# stm32f103_ethernet_shield.net
KiCad netlist of a schematic drawn in EAGLE
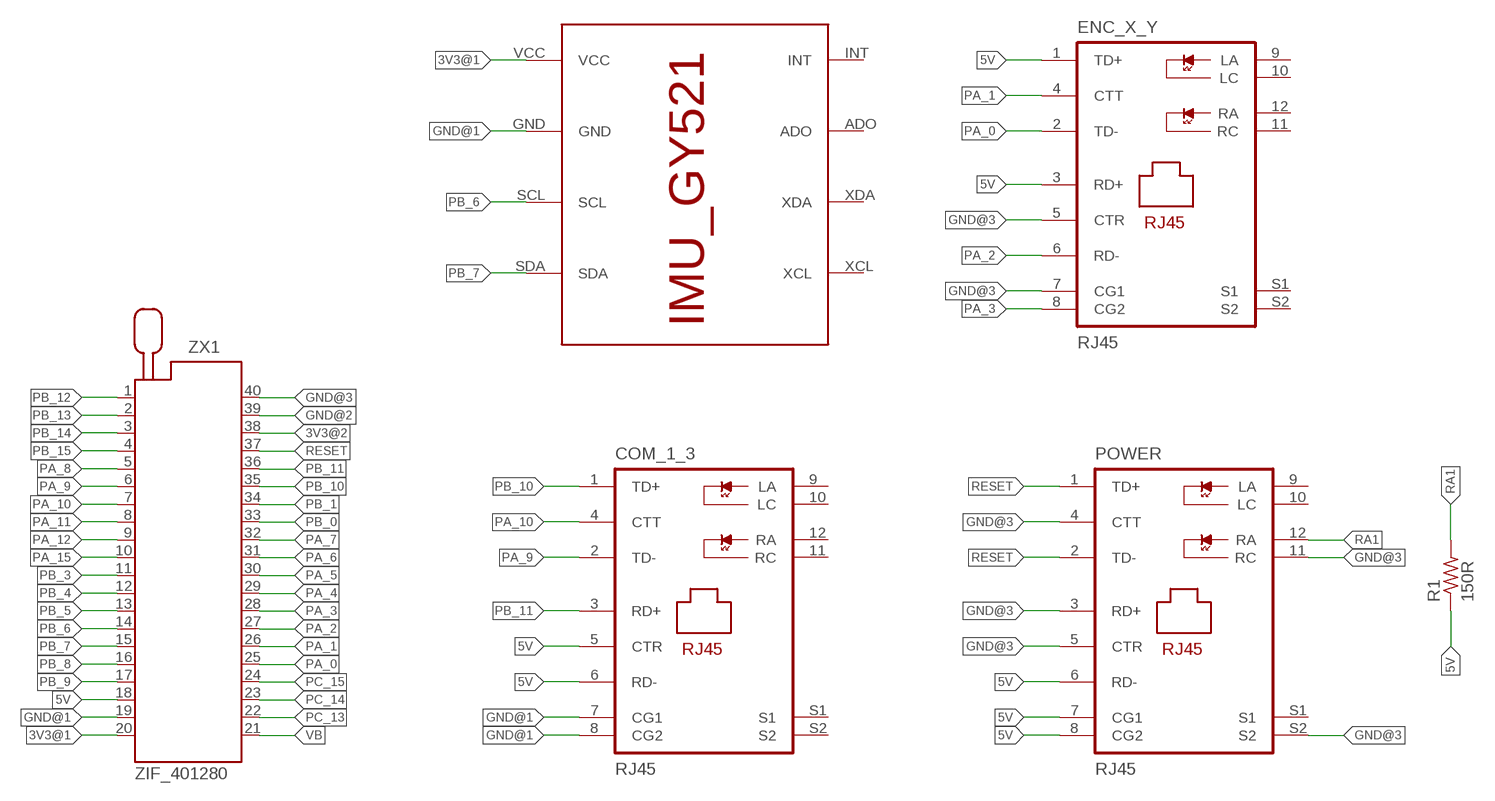
[diagram p0: schematic, sheet 1]

(export (version "E")
  (design (tool "Eeschema 10.0.6"))
  (components
    (comp (ref "COM_1_3")
      (value "RJ45")
      (footprint "eagle-import:J0-A_B_F")
      (libsource (lib "eagle-import") (part "RJ45_METAL_LEDS"))
    )
    (comp (ref "ENC_X_Y")
      (value "RJ45")
      (footprint "eagle-import:J0-A_B_F")
      (fields (field (name "SPICEPREFIX") "X"))
      (libsource (lib "eagle-import") (part "RJ45_METAL_LEDS"))
    )
    (comp (ref "MPU6050")
      (value "IMU_ROBOCON_GY521")
      (footprint "eagle-import:IMU_GY521")
      (libsource (lib "eagle-import") (part "IMU_ROBOCON_GY521"))
    )
    (comp (ref "POWER")
      (value "RJ45")
      (footprint "eagle-import:J0-A_B_F")
      (libsource (lib "eagle-import") (part "RJ45_METAL_LEDS"))
    )
    (comp (ref "R1")
      (value "150R")
      (footprint "eagle-import:0204_7")
      (libsource (lib "eagle-import") (part "RES-7"))
    )
    (comp (ref "ZX1")
      (value "ZIF_401280")
      (footprint "eagle-import:240-1280-00-0602J")
      (libsource (lib "eagle-import") (part "ZIF_401280"))
    )
  )
  (nets
    (net (code "1") (name "3V3@1") (class "Default")
      (node (ref "MPU6050") (pin "VCC") (pinfunction "VCC_VCC") (pintype "bidirectional"))
      (node (ref "ZX1") (pin "20") (pinfunction "20_20") (pintype "passive"))
    )
    (net (code "2") (name "3V3@2") (class "Default")
      (node (ref "ZX1") (pin "38") (pinfunction "38_38") (pintype "passive"))
    )
    (net (code "3") (name "5V") (class "Default")
      (node (ref "COM_1_3") (pin "5") (pinfunction "CTR_5") (pintype "passive"))
      (node (ref "COM_1_3") (pin "6") (pinfunction "RD-_6") (pintype "passive"))
      (node (ref "ENC_X_Y") (pin "1") (pinfunction "TD+_1") (pintype "passive"))
      (node (ref "ENC_X_Y") (pin "3") (pinfunction "RD+_3") (pintype "passive"))
      (node (ref "POWER") (pin "6") (pinfunction "RD-_6") (pintype "passive"))
      (node (ref "POWER") (pin "7") (pinfunction "CG1_7") (pintype "passive"))
      (node (ref "POWER") (pin "8") (pinfunction "CG2_8") (pintype "passive"))
      (node (ref "R1") (pin "1") (pinfunction "1_1") (pintype "passive"))
      (node (ref "ZX1") (pin "18") (pinfunction "18_18") (pintype "passive"))
    )
    (net (code "4") (name "GND@1") (class "Default")
      (node (ref "COM_1_3") (pin "7") (pinfunction "CG1_7") (pintype "passive"))
      (node (ref "COM_1_3") (pin "8") (pinfunction "CG2_8") (pintype "passive"))
      (node (ref "MPU6050") (pin "GND") (pinfunction "GND_GND") (pintype "bidirectional"))
      (node (ref "ZX1") (pin "19") (pinfunction "19_19") (pintype "passive"))
    )
    (net (code "5") (name "GND@2") (class "Default")
      (node (ref "ZX1") (pin "39") (pinfunction "39_39") (pintype "passive"))
    )
    (net (code "6") (name "GND@3") (class "Default")
      (node (ref "ENC_X_Y") (pin "5") (pinfunction "CTR_5") (pintype "passive"))
      (node (ref "ENC_X_Y") (pin "7") (pinfunction "CG1_7") (pintype "passive"))
      (node (ref "POWER") (pin "11") (pinfunction "RC_11") (pintype "passive"))
      (node (ref "POWER") (pin "3") (pinfunction "RD+_3") (pintype "passive"))
      (node (ref "POWER") (pin "4") (pinfunction "CTT_4") (pintype "passive"))
      (node (ref "POWER") (pin "5") (pinfunction "CTR_5") (pintype "passive"))
      (node (ref "POWER") (pin "S2") (pinfunction "S2_S2") (pintype "passive"))
      (node (ref "ZX1") (pin "40") (pinfunction "40_40") (pintype "passive"))
    )
    (net (code "7") (name "PA_0") (class "Default")
      (node (ref "ENC_X_Y") (pin "2") (pinfunction "TD-_2") (pintype "passive"))
      (node (ref "ZX1") (pin "25") (pinfunction "25_25") (pintype "passive"))
    )
    (net (code "8") (name "PA_1") (class "Default")
      (node (ref "ENC_X_Y") (pin "4") (pinfunction "CTT_4") (pintype "passive"))
      (node (ref "ZX1") (pin "26") (pinfunction "26_26") (pintype "passive"))
    )
    (net (code "9") (name "PA_2") (class "Default")
      (node (ref "ENC_X_Y") (pin "6") (pinfunction "RD-_6") (pintype "passive"))
      (node (ref "ZX1") (pin "27") (pinfunction "27_27") (pintype "passive"))
    )
    (net (code "10") (name "PA_3") (class "Default")
      (node (ref "ENC_X_Y") (pin "8") (pinfunction "CG2_8") (pintype "passive"))
      (node (ref "ZX1") (pin "28") (pinfunction "28_28") (pintype "passive"))
    )
    (net (code "11") (name "PA_4") (class "Default")
      (node (ref "ZX1") (pin "29") (pinfunction "29_29") (pintype "passive"))
    )
    (net (code "12") (name "PA_5") (class "Default")
      (node (ref "ZX1") (pin "30") (pinfunction "30_30") (pintype "passive"))
    )
    (net (code "13") (name "PA_6") (class "Default")
      (node (ref "ZX1") (pin "31") (pinfunction "31_31") (pintype "passive"))
    )
    (net (code "14") (name "PA_7") (class "Default")
      (node (ref "ZX1") (pin "32") (pinfunction "32_32") (pintype "passive"))
    )
    (net (code "15") (name "PA_8") (class "Default")
      (node (ref "ZX1") (pin "5") (pinfunction "5_5") (pintype "passive"))
    )
    (net (code "16") (name "PA_9") (class "Default")
      (node (ref "COM_1_3") (pin "2") (pinfunction "TD-_2") (pintype "passive"))
      (node (ref "ZX1") (pin "6") (pinfunction "6_6") (pintype "passive"))
    )
    (net (code "17") (name "PA_10") (class "Default")
      (node (ref "COM_1_3") (pin "4") (pinfunction "CTT_4") (pintype "passive"))
      (node (ref "ZX1") (pin "7") (pinfunction "7_7") (pintype "passive"))
    )
    (net (code "18") (name "PA_11") (class "Default")
      (node (ref "ZX1") (pin "8") (pinfunction "8_8") (pintype "passive"))
    )
    (net (code "19") (name "PA_12") (class "Default")
      (node (ref "ZX1") (pin "9") (pinfunction "9_9") (pintype "passive"))
    )
    (net (code "20") (name "PA_15") (class "Default")
      (node (ref "ZX1") (pin "10") (pinfunction "10_10") (pintype "passive"))
    )
    (net (code "21") (name "PB_0") (class "Default")
      (node (ref "ZX1") (pin "33") (pinfunction "33_33") (pintype "passive"))
    )
    (net (code "22") (name "PB_1") (class "Default")
      (node (ref "ZX1") (pin "34") (pinfunction "34_34") (pintype "passive"))
    )
    (net (code "23") (name "PB_3") (class "Default")
      (node (ref "ZX1") (pin "11") (pinfunction "11_11") (pintype "passive"))
    )
    (net (code "24") (name "PB_4") (class "Default")
      (node (ref "ZX1") (pin "12") (pinfunction "12_12") (pintype "passive"))
    )
    (net (code "25") (name "PB_5") (class "Default")
      (node (ref "ZX1") (pin "13") (pinfunction "13_13") (pintype "passive"))
    )
    (net (code "26") (name "PB_6") (class "Default")
      (node (ref "MPU6050") (pin "SCL") (pinfunction "SCL_SCL") (pintype "bidirectional"))
      (node (ref "ZX1") (pin "14") (pinfunction "14_14") (pintype "passive"))
    )
    (net (code "27") (name "PB_7") (class "Default")
      (node (ref "MPU6050") (pin "SDA") (pinfunction "SDA_SDA") (pintype "bidirectional"))
      (node (ref "ZX1") (pin "15") (pinfunction "15_15") (pintype "passive"))
    )
    (net (code "28") (name "PB_8") (class "Default")
      (node (ref "ZX1") (pin "16") (pinfunction "16_16") (pintype "passive"))
    )
    (net (code "29") (name "PB_9") (class "Default")
      (node (ref "ZX1") (pin "17") (pinfunction "17_17") (pintype "passive"))
    )
    (net (code "30") (name "PB_10") (class "Default")
      (node (ref "COM_1_3") (pin "1") (pinfunction "TD+_1") (pintype "passive"))
      (node (ref "ZX1") (pin "35") (pinfunction "35_35") (pintype "passive"))
    )
    (net (code "31") (name "PB_11") (class "Default")
      (node (ref "COM_1_3") (pin "3") (pinfunction "RD+_3") (pintype "passive"))
      (node (ref "ZX1") (pin "36") (pinfunction "36_36") (pintype "passive"))
    )
    (net (code "32") (name "PB_12") (class "Default")
      (node (ref "ZX1") (pin "1") (pinfunction "1_1") (pintype "passive"))
    )
    (net (code "33") (name "PB_13") (class "Default")
      (node (ref "ZX1") (pin "2") (pinfunction "2_2") (pintype "passive"))
    )
    (net (code "34") (name "PB_14") (class "Default")
      (node (ref "ZX1") (pin "3") (pinfunction "3_3") (pintype "passive"))
    )
    (net (code "35") (name "PB_15") (class "Default")
      (node (ref "ZX1") (pin "4") (pinfunction "4_4") (pintype "passive"))
    )
    (net (code "36") (name "PC_13") (class "Default")
      (node (ref "ZX1") (pin "22") (pinfunction "22_22") (pintype "passive"))
    )
    (net (code "37") (name "PC_14") (class "Default")
      (node (ref "ZX1") (pin "23") (pinfunction "23_23") (pintype "passive"))
    )
    (net (code "38") (name "PC_15") (class "Default")
      (node (ref "ZX1") (pin "24") (pinfunction "24_24") (pintype "passive"))
    )
    (net (code "39") (name "RA1") (class "Default")
      (node (ref "POWER") (pin "12") (pinfunction "RA_12") (pintype "passive"))
      (node (ref "R1") (pin "2") (pinfunction "2_2") (pintype "passive"))
    )
    (net (code "40") (name "RESET") (class "Default")
      (node (ref "POWER") (pin "1") (pinfunction "TD+_1") (pintype "passive"))
      (node (ref "POWER") (pin "2") (pinfunction "TD-_2") (pintype "passive"))
      (node (ref "ZX1") (pin "37") (pinfunction "37_37") (pintype "passive"))
    )
    (net (code "41") (name "VB") (class "Default")
      (node (ref "ZX1") (pin "21") (pinfunction "21_21") (pintype "passive"))
    )
    (net (code "42") (name "unconnected-(COM_1_3-LA-Pad9)") (class "Default")
      (node (ref "COM_1_3") (pin "9") (pinfunction "LA_9") (pintype "passive"))
    )
    (net (code "43") (name "unconnected-(COM_1_3-LC-Pad10)") (class "Default")
      (node (ref "COM_1_3") (pin "10") (pinfunction "LC_10") (pintype "passive"))
    )
    (net (code "44") (name "unconnected-(COM_1_3-PadS1)") (class "Default")
      (node (ref "COM_1_3") (pin "S1") (pinfunction "S1_S1") (pintype "passive"))
    )
    (net (code "45") (name "unconnected-(COM_1_3-PadS2)") (class "Default")
      (node (ref "COM_1_3") (pin "S2") (pinfunction "S2_S2") (pintype "passive"))
    )
    (net (code "46") (name "unconnected-(COM_1_3-RA-Pad12)") (class "Default")
      (node (ref "COM_1_3") (pin "12") (pinfunction "RA_12") (pintype "passive"))
    )
    (net (code "47") (name "unconnected-(COM_1_3-RC-Pad11)") (class "Default")
      (node (ref "COM_1_3") (pin "11") (pinfunction "RC_11") (pintype "passive"))
    )
    (net (code "48") (name "unconnected-(ENC_X_Y-LA-Pad9)") (class "Default")
      (node (ref "ENC_X_Y") (pin "9") (pinfunction "LA_9") (pintype "passive"))
    )
    (net (code "49") (name "unconnected-(ENC_X_Y-LC-Pad10)") (class "Default")
      (node (ref "ENC_X_Y") (pin "10") (pinfunction "LC_10") (pintype "passive"))
    )
    (net (code "50") (name "unconnected-(ENC_X_Y-PadS1)") (class "Default")
      (node (ref "ENC_X_Y") (pin "S1") (pinfunction "S1_S1") (pintype "passive"))
    )
    (net (code "51") (name "unconnected-(ENC_X_Y-PadS2)") (class "Default")
      (node (ref "ENC_X_Y") (pin "S2") (pinfunction "S2_S2") (pintype "passive"))
    )
    (net (code "52") (name "unconnected-(ENC_X_Y-RA-Pad12)") (class "Default")
      (node (ref "ENC_X_Y") (pin "12") (pinfunction "RA_12") (pintype "passive"))
    )
    (net (code "53") (name "unconnected-(ENC_X_Y-RC-Pad11)") (class "Default")
      (node (ref "ENC_X_Y") (pin "11") (pinfunction "RC_11") (pintype "passive"))
    )
    (net (code "54") (name "unconnected-(MPU6050-PadADO)") (class "Default")
      (node (ref "MPU6050") (pin "ADO") (pinfunction "ADO_ADO") (pintype "bidirectional"))
    )
    (net (code "55") (name "unconnected-(MPU6050-PadINT)") (class "Default")
      (node (ref "MPU6050") (pin "INT") (pinfunction "INT_INT") (pintype "bidirectional"))
    )
    (net (code "56") (name "unconnected-(MPU6050-PadXCL)") (class "Default")
      (node (ref "MPU6050") (pin "XCL") (pinfunction "XCL_XCL") (pintype "bidirectional"))
    )
    (net (code "57") (name "unconnected-(MPU6050-PadXDA)") (class "Default")
      (node (ref "MPU6050") (pin "XDA") (pinfunction "XDA_XDA") (pintype "bidirectional"))
    )
    (net (code "58") (name "unconnected-(POWER-LA-Pad9)") (class "Default")
      (node (ref "POWER") (pin "9") (pinfunction "LA_9") (pintype "passive"))
    )
    (net (code "59") (name "unconnected-(POWER-LC-Pad10)") (class "Default")
      (node (ref "POWER") (pin "10") (pinfunction "LC_10") (pintype "passive"))
    )
    (net (code "60") (name "unconnected-(POWER-PadS1)") (class "Default")
      (node (ref "POWER") (pin "S1") (pinfunction "S1_S1") (pintype "passive"))
    )
  )
)
